# Acoustics_Preamp.net
KiCad netlist of a schematic drawn in Altium Designer
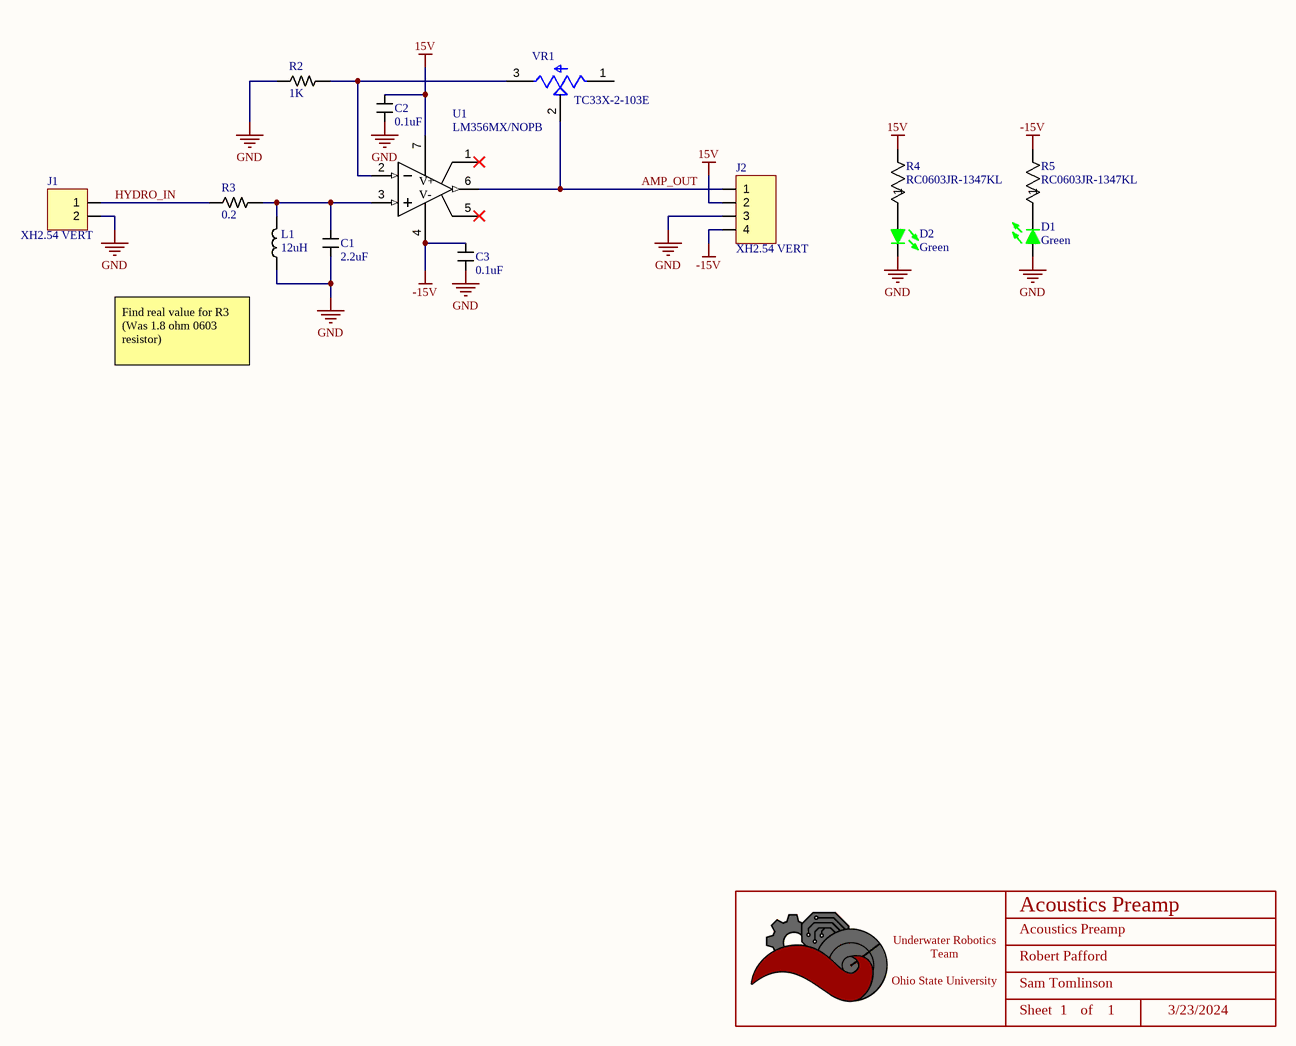
[diagram p0: Acoustics_Preamp.SchDoc]

(export (version "E")
  (design (tool "Eeschema 10.0.6"))
  (components
    (comp (ref "*")
      (value "Title_Block")
      (footprint "LOGO")
      (description "UWRT Schematic Title Block Template\r\n\r\nCreated June 2021, Dylan Trainor")
      (libsource (lib "UWRT") (part "Title_Block"))
    )
    (comp (ref "C1")
      (value "2.2uF")
      (footprint "CAPACITOR_0603")
      (description "CAP CER 2.2PF 50V C0G/NP0 0603")
      (fields
        (field (name "TOLERANCE") "+/- 20%")
        (field (name "VOLTAGE") "6.3V")
        (field (name "MADE BY") "Flip B")
      )
      (libsource (lib "Capacitors") (part "CAPACITOR_22uF_0603"))
    )
    (comp (ref "C2")
      (value "0.1uF")
      (footprint "CAPACITOR_0603")
      (description "Cap 100nF 25V +/-10%\r\nCeramic 0603")
      (fields
        (field (name "TOLERANCE") "+/- 10%")
        (field (name "VOLTAGE") "6.3V")
        (field (name "MADE BY") "Flip B")
      )
      (libsource (lib "Capacitors") (part "CAPACITOR_0.1uF_0603_25V"))
    )
    (comp (ref "C3")
      (value "0.1uF")
      (footprint "CAPACITOR_0603")
      (description "Cap 100nF 25V +/-10%\r\nCeramic 0603")
      (fields
        (field (name "TOLERANCE") "+/- 10%")
        (field (name "VOLTAGE") "6.3V")
        (field (name "MADE BY") "Flip B")
      )
      (libsource (lib "Capacitors") (part "CAPACITOR_0.1uF_0603_25V"))
    )
    (comp (ref "D1")
      (value "150060GS75000")
      (footprint "LED_0603")
      (description "LED Green Vf= 3.2V If = 0.025A\r\n150060GS75000")
      (fields (field (name "COLOR") "Green") (field (name "MADE BY") "Flip B"))
      (libsource (lib "Diodes") (part "LED_Green_0603_3.2V"))
    )
    (comp (ref "D2")
      (value "150060GS75000")
      (footprint "LED_0603")
      (description "LED Green Vf= 3.2V If = 0.025A\r\n150060GS75000")
      (fields (field (name "COLOR") "Green") (field (name "MADE BY") "Flip B"))
      (libsource (lib "Diodes") (part "LED_Green_0603_3.2V"))
    )
    (comp (ref "J1")
      (value "XH2.54 VERT")
      (footprint "CONN_JST_XH254_2POS_VERT")
      (description "JST XH 2.54mm Pitch 2 Pos Vertical")
      (fields (field (name "MANUFACTURER") "JST") (field (name "CREATED BY") "Robert P"))
      (libsource (lib "Connectors") (part "CONN_JST_XH254_2POS_VERT"))
    )
    (comp (ref "J2")
      (value "XH2.54 VERT")
      (footprint "CONN_JST_XH254_4POS_VERT")
      (description "JST XH 2.54mm Pitch 4 Pos Vertical")
      (fields (field (name "MANUFACTURER") "JST") (field (name "CREATED BY") "Robert P"))
      (libsource (lib "Connectors") (part "CONN_JST_XH254_4POS_VERT"))
    )
    (comp (ref "L1")
      (value "12uH")
      (footprint "INDUCTOR_0603")
      (description "12 µH Shielded Multilayer Inductor 10 mA 1.8Ohm Max 0603 (1608 Metric)")
      (fields
        (field (name "TOLERANCE") "+/- 20%")
        (field (name "Comment") "FIXED IND 12UH 10MA 1.8 OHM SMD")
        (field (name "MADE BY") "Robert Pafford")
      )
      (libsource (lib "Inductors") (part "INDUCTOR_12uH_0603"))
    )
    (comp (ref "R2")
      (value "1k Ohm 5% 1/8W")
      (footprint "RESISTOR_0603")
      (description "RES 1.8 OHM 5% 1/8W 0603")
      (fields
        (field (name "TOLERANCE") "+/- 5%")
        (field (name "VALUE  (OHMS)") "1K")
        (field (name "MADE BY") "Robert Pafford")
      )
      (libsource (lib "Resistors") (part "RESISTOR_1K_0603"))
    )
    (comp (ref "R3")
      (value "0.2 Ohm 5% 1/8W")
      (footprint "RESISTOR_0603")
      (description "RES 0.2 OHM 5% 1/8W 0603")
      (fields
        (field (name "TOLERANCE") "+/- 5%")
        (field (name "VALUE  (OHMS)") "0.2")
        (field (name "MADE BY") "Robert Pafford")
      )
      (libsource (lib "Resistors") (part "RESISTOR_0.2_0603"))
    )
    (comp (ref "R4")
      (value "RC0603JR-1347KL")
      (footprint "RESISTOR_0603")
      (description "47kohm 0603 1/10w")
      (fields (field (name "COPYRIGHT") "Copyright (C) 2024 Ultra Librarian. All rights reserved."))
      (libsource (lib "Resistors") (part "RC0603JR-1347KL"))
    )
    (comp (ref "R5")
      (value "RC0603JR-1347KL")
      (footprint "RESISTOR_0603")
      (description "47kohm 0603 1/10w")
      (fields (field (name "COPYRIGHT") "Copyright (C) 2024 Ultra Librarian. All rights reserved."))
      (libsource (lib "Resistors") (part "RC0603JR-1347KL"))
    )
    (comp (ref "U1")
      (value "LM356MX/NOPB")
      (footprint "SOIC-8")
      (description "IC OPAMP JFET 1 CIRCUIT 8SOIC")
      (fields
        (field (name "PARTNUMBER") "LM8261M5X/NOPB")
        (field (name "MANUFACTURER") "Texas Instruments")
        (field (name "CREATED BY") "Dylan T")
      )
      (libsource (lib "Integrated Circuits") (part "LM356MX/NOPB"))
    )
    (comp (ref "VR1")
      (value "TC33X-2-103E")
      (footprint "TRIM_TC33X-2-203E")
      (description "20 kOhms 0.1W, 1/10W J Lead Surface Mount Trimmer Potentiometer Cermet 1 Turn Top Adjustment")
      (fields (field (name "MF") "Bourns") (field (name "DIGI-KEY_PART_NUMBER") "TC33X-2-203ECT-ND"))
      (libsource (lib "Resistors") (part "TC33X-2-203E"))
    )
  )
  (nets
    (net (code "1") (name "-15V") (class "Default")
      (node (ref "C3") (pin "1") (pinfunction "1_1") (pintype "passive"))
      (node (ref "J2") (pin "4") (pinfunction "4_4") (pintype "passive"))
      (node (ref "R5") (pin "2") (pinfunction "2_2") (pintype "passive"))
      (node (ref "U1") (pin "4") (pinfunction "V-_4") (pintype "power_in"))
    )
    (net (code "3") (name "/AMP_OUT") (class "Default")
      (node (ref "J2") (pin "1") (pinfunction "1_1") (pintype "passive"))
      (node (ref "U1") (pin "6") (pinfunction "OUT_6") (pintype "output"))
      (node (ref "VR1") (pin "2") (pinfunction "W_2") (pintype "passive"))
    )
    (net (code "4") (name "/HYDRO_IN") (class "Default")
      (node (ref "J1") (pin "1") (pinfunction "1_1") (pintype "passive"))
      (node (ref "R3") (pin "2") (pinfunction "2_2") (pintype "passive"))
    )
    (net (code "5") (name "15V") (class "Default")
      (node (ref "C2") (pin "1") (pinfunction "1_1") (pintype "passive"))
      (node (ref "J2") (pin "2") (pinfunction "2_2") (pintype "passive"))
      (node (ref "R4") (pin "2") (pinfunction "2_2") (pintype "passive"))
      (node (ref "U1") (pin "7") (pinfunction "V+_7") (pintype "power_in"))
    )
    (net (code "6") (name "GND") (class "Default")
      (node (ref "C1") (pin "2") (pinfunction "2_2") (pintype "passive"))
      (node (ref "C2") (pin "2") (pinfunction "2_2") (pintype "passive"))
      (node (ref "C3") (pin "2") (pinfunction "2_2") (pintype "passive"))
      (node (ref "D1") (pin "1") (pinfunction "1_1") (pintype "passive"))
      (node (ref "D2") (pin "2") (pinfunction "2_2") (pintype "passive"))
      (node (ref "J1") (pin "2") (pinfunction "2_2") (pintype "passive"))
      (node (ref "J2") (pin "3") (pinfunction "3_3") (pintype "passive"))
      (node (ref "L1") (pin "2") (pinfunction "2_2") (pintype "passive"))
      (node (ref "R2") (pin "2") (pinfunction "2_2") (pintype "passive"))
    )
    (net (code "7") (name "Net-(D1-Pad2)") (class "Default")
      (node (ref "D1") (pin "2") (pinfunction "2_2") (pintype "passive"))
      (node (ref "R5") (pin "1") (pinfunction "1_1") (pintype "passive"))
    )
    (net (code "8") (name "Net-(D2-Pad1)") (class "Default")
      (node (ref "D2") (pin "1") (pinfunction "1_1") (pintype "passive"))
      (node (ref "R4") (pin "1") (pinfunction "1_1") (pintype "passive"))
    )
    (net (code "9") (name "Net-(U1-IN+)") (class "Default")
      (node (ref "C1") (pin "1") (pinfunction "1_1") (pintype "passive"))
      (node (ref "L1") (pin "1") (pinfunction "1_1") (pintype "passive"))
      (node (ref "R3") (pin "1") (pinfunction "1_1") (pintype "passive"))
      (node (ref "U1") (pin "3") (pinfunction "IN+_3") (pintype "input"))
    )
    (net (code "10") (name "Net-(U1-IN-)") (class "Default")
      (node (ref "R2") (pin "1") (pinfunction "1_1") (pintype "passive"))
      (node (ref "U1") (pin "2") (pinfunction "IN-_2") (pintype "input"))
      (node (ref "VR1") (pin "3") (pinfunction "CW_3") (pintype "passive"))
    )
    (net (code "11") (name "unconnected-(U1-Balance-Pad1)") (class "Default")
      (node (ref "U1") (pin "1") (pinfunction "Balance_1") (pintype "passive+no_connect"))
    )
    (net (code "12") (name "unconnected-(U1-Balance-Pad5)") (class "Default")
      (node (ref "U1") (pin "5") (pinfunction "Balance_5") (pintype "passive+no_connect"))
    )
    (net (code "13") (name "unconnected-(VR1-CCW-Pad1)") (class "Default")
      (node (ref "VR1") (pin "1") (pinfunction "CCW_1") (pintype "passive"))
    )
  )
)
